# rogerbeep.net
KiCad netlist of a schematic drawn in EAGLE
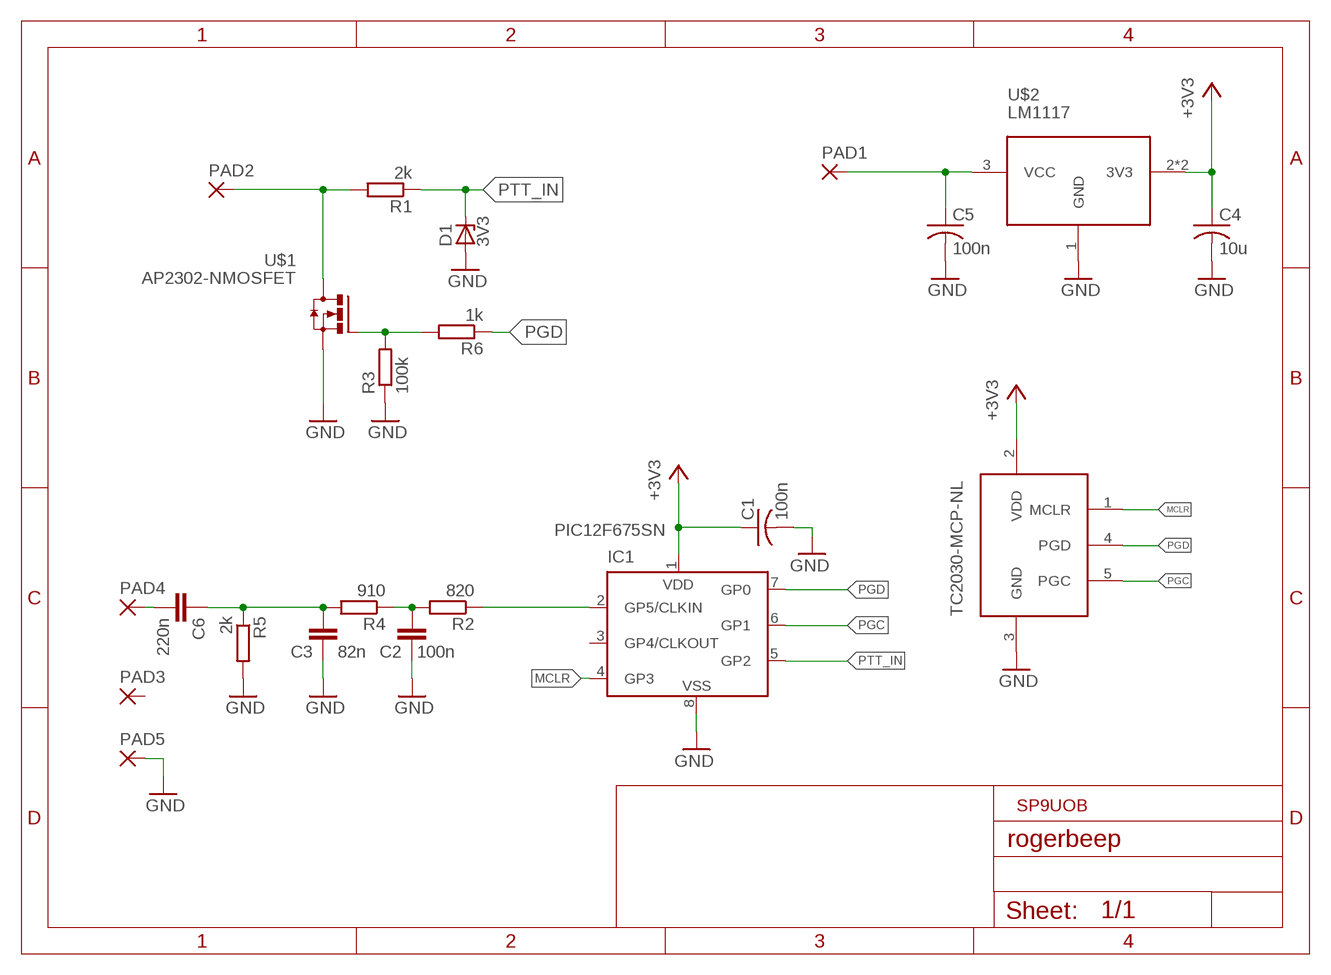
[diagram p0: schematic, sheet 1]

(export (version "E")
  (design (tool "Eeschema 10.0.6"))
  (components
    (comp (ref "C1")
      (value "100n")
      (footprint "eagle-import:C0805")
      (libsource (lib "eagle-import") (part "C-USC0805"))
    )
    (comp (ref "C2")
      (value "100n")
      (footprint "eagle-import:C0603")
      (libsource (lib "eagle-import") (part "C-EUC0603"))
    )
    (comp (ref "C3")
      (value "82n")
      (footprint "eagle-import:C0603")
      (libsource (lib "eagle-import") (part "C-EUC0603"))
    )
    (comp (ref "C4")
      (value "10u")
      (footprint "eagle-import:C0805")
      (libsource (lib "eagle-import") (part "C-USC0805"))
    )
    (comp (ref "C5")
      (value "100n")
      (footprint "eagle-import:C0805")
      (libsource (lib "eagle-import") (part "C-USC0805"))
    )
    (comp (ref "C6")
      (value "220n")
      (footprint "eagle-import:C0603")
      (libsource (lib "eagle-import") (part "C-EUC0603"))
    )
    (comp (ref "D1")
      (value "3V3")
      (footprint "eagle-import:SOT23")
      (libsource (lib "eagle-import") (part "ZENER-DIODESOT23"))
    )
    (comp (ref "IC1")
      (value "PIC12F675SN")
      (footprint "eagle-import:SO-08")
      (fields (field (name "MF") "MICROCHIP") (field (name "MPN") "PIC12F675-E/SN"))
      (libsource (lib "eagle-import") (part "PIC12F6SN75"))
    )
    (comp (ref "PAD1")
      (value "SMD5")
      (footprint "eagle-import:SMD2,54-5,08")
      (libsource (lib "eagle-import") (part "SMD5"))
    )
    (comp (ref "PAD2")
      (value "SMD5")
      (footprint "eagle-import:SMD2,54-5,08")
      (libsource (lib "eagle-import") (part "SMD5"))
    )
    (comp (ref "PAD3")
      (value "SMD5")
      (footprint "eagle-import:SMD2,54-5,08")
      (libsource (lib "eagle-import") (part "SMD5"))
    )
    (comp (ref "PAD4")
      (value "SMD2")
      (footprint "eagle-import:SMD1,27-2,54")
      (libsource (lib "eagle-import") (part "SMD2"))
    )
    (comp (ref "PAD5")
      (value "SMD2")
      (footprint "eagle-import:SMD1,27-2,54")
      (libsource (lib "eagle-import") (part "SMD2"))
    )
    (comp (ref "R1")
      (value "2k")
      (footprint "eagle-import:R0603")
      (libsource (lib "eagle-import") (part "R-EU_R0603"))
    )
    (comp (ref "R2")
      (value "820")
      (footprint "eagle-import:R0603")
      (libsource (lib "eagle-import") (part "R-EU_R0603"))
    )
    (comp (ref "R3")
      (value "100k")
      (footprint "eagle-import:R0603")
      (libsource (lib "eagle-import") (part "R-EU_R0603"))
    )
    (comp (ref "R4")
      (value "910")
      (footprint "eagle-import:R0603")
      (libsource (lib "eagle-import") (part "R-EU_R0603"))
    )
    (comp (ref "R5")
      (value "2k")
      (footprint "eagle-import:R0603")
      (libsource (lib "eagle-import") (part "R-EU_R0603"))
    )
    (comp (ref "R6")
      (value "1k")
      (footprint "eagle-import:R0603")
      (libsource (lib "eagle-import") (part "R-EU_R0603"))
    )
    (comp (ref "U$1")
      (value "AP2302-NMOSFET")
      (footprint "eagle-import:SOT23-3")
      (libsource (lib "eagle-import") (part "AP2302-NMOSFET"))
    )
    (comp (ref "U$2")
      (value "LM1117")
      (footprint "eagle-import:SOT223-3")
      (libsource (lib "eagle-import") (part "LM1117"))
    )
    (comp (ref "U$5")
      (value "TC2030-MCP")
      (footprint "eagle-import:TC2030-IDC-NL")
      (libsource (lib "eagle-import") (part "TC2030-MCP"))
    )
  )
  (nets
    (net (code "1") (name "+3V3") (class "Default")
      (node (ref "C1") (pin "1") (pinfunction "1_1") (pintype "passive"))
      (node (ref "C4") (pin "1") (pinfunction "1_1") (pintype "passive"))
      (node (ref "IC1") (pin "1") (pinfunction "VDD_1") (pintype "power_in"))
      (node (ref "U$2") (pin "2") (pinfunction "3V3_2") (pintype "output"))
      (node (ref "U$2") (pin "4") (pinfunction "3V3_4") (pintype "output"))
      (node (ref "U$5") (pin "2") (pinfunction "VDD_2") (pintype "power_in"))
    )
    (net (code "2") (name "GND") (class "Default")
      (node (ref "C1") (pin "2") (pinfunction "2_2") (pintype "passive"))
      (node (ref "C2") (pin "1") (pinfunction "1_1") (pintype "passive"))
      (node (ref "C3") (pin "1") (pinfunction "1_1") (pintype "passive"))
      (node (ref "C4") (pin "2") (pinfunction "2_2") (pintype "passive"))
      (node (ref "C5") (pin "2") (pinfunction "2_2") (pintype "passive"))
      (node (ref "D1") (pin "1") (pinfunction "A_1") (pintype "passive"))
      (node (ref "IC1") (pin "8") (pinfunction "VSS_8") (pintype "power_in"))
      (node (ref "PAD5") (pin "1") (pinfunction "P_1") (pintype "passive"))
      (node (ref "R3") (pin "1") (pinfunction "1_1") (pintype "passive"))
      (node (ref "R5") (pin "2") (pinfunction "2_2") (pintype "passive"))
      (node (ref "U$1") (pin "2") (pinfunction "S1_2") (pintype "passive"))
      (node (ref "U$2") (pin "1") (pinfunction "GND_1") (pintype "power_in"))
      (node (ref "U$5") (pin "3") (pinfunction "GND_3") (pintype "power_in"))
    )
    (net (code "3") (name "MCLR") (class "Default")
      (node (ref "IC1") (pin "4") (pinfunction "GP3_4") (pintype "input"))
      (node (ref "U$5") (pin "1") (pinfunction "MCLR_1") (pintype "bidirectional"))
    )
    (net (code "4") (name "Net-(C2-Pad2)") (class "Default")
      (node (ref "C2") (pin "2") (pinfunction "2_2") (pintype "passive"))
      (node (ref "R2") (pin "2") (pinfunction "2_2") (pintype "passive"))
      (node (ref "R4") (pin "1") (pinfunction "1_1") (pintype "passive"))
    )
    (net (code "5") (name "Net-(C3-Pad2)") (class "Default")
      (node (ref "C3") (pin "2") (pinfunction "2_2") (pintype "passive"))
      (node (ref "C6") (pin "1") (pinfunction "1_1") (pintype "passive"))
      (node (ref "R4") (pin "2") (pinfunction "2_2") (pintype "passive"))
      (node (ref "R5") (pin "1") (pinfunction "1_1") (pintype "passive"))
    )
    (net (code "6") (name "Net-(IC1-GP5{slash}CLKIN)") (class "Default")
      (node (ref "IC1") (pin "2") (pinfunction "GP5/CLKIN_2") (pintype "bidirectional"))
      (node (ref "R2") (pin "1") (pinfunction "1_1") (pintype "passive"))
    )
    (net (code "7") (name "Net-(PAD1-P)") (class "Default")
      (node (ref "C5") (pin "1") (pinfunction "1_1") (pintype "passive"))
      (node (ref "PAD1") (pin "1") (pinfunction "P_1") (pintype "passive"))
      (node (ref "U$2") (pin "3") (pinfunction "VCC_3") (pintype "power_in"))
    )
    (net (code "8") (name "Net-(PAD2-P)") (class "Default")
      (node (ref "PAD2") (pin "1") (pinfunction "P_1") (pintype "passive"))
      (node (ref "R1") (pin "2") (pinfunction "2_2") (pintype "passive"))
      (node (ref "U$1") (pin "3") (pinfunction "D1_3") (pintype "passive"))
    )
    (net (code "9") (name "Net-(PAD4-P)") (class "Default")
      (node (ref "C6") (pin "2") (pinfunction "2_2") (pintype "passive"))
      (node (ref "PAD4") (pin "1") (pinfunction "P_1") (pintype "passive"))
    )
    (net (code "10") (name "Net-(U$1-G1)") (class "Default")
      (node (ref "R3") (pin "2") (pinfunction "2_2") (pintype "passive"))
      (node (ref "R6") (pin "2") (pinfunction "2_2") (pintype "passive"))
      (node (ref "U$1") (pin "1") (pinfunction "G1_1") (pintype "passive"))
    )
    (net (code "11") (name "PGC") (class "Default")
      (node (ref "IC1") (pin "6") (pinfunction "GP1_6") (pintype "bidirectional"))
      (node (ref "U$5") (pin "5") (pinfunction "PGC_5") (pintype "bidirectional"))
    )
    (net (code "12") (name "PGD") (class "Default")
      (node (ref "IC1") (pin "7") (pinfunction "GP0_7") (pintype "bidirectional"))
      (node (ref "R6") (pin "1") (pinfunction "1_1") (pintype "passive"))
      (node (ref "U$5") (pin "4") (pinfunction "PGD_4") (pintype "bidirectional"))
    )
    (net (code "13") (name "PTT_IN") (class "Default")
      (node (ref "D1") (pin "3") (pinfunction "C_3") (pintype "passive"))
      (node (ref "IC1") (pin "5") (pinfunction "GP2_5") (pintype "bidirectional"))
      (node (ref "R1") (pin "1") (pinfunction "1_1") (pintype "passive"))
    )
    (net (code "14") (name "unconnected-(IC1-GP4{slash}CLKOUT-Pad3)") (class "Default")
      (node (ref "IC1") (pin "3") (pinfunction "GP4/CLKOUT_3") (pintype "bidirectional"))
    )
    (net (code "15") (name "unconnected-(PAD3-P-Pad1)") (class "Default")
      (node (ref "PAD3") (pin "1") (pinfunction "P_1") (pintype "passive"))
    )
  )
)
